# makeblock_stepper_driver.net
KiCad netlist of a schematic drawn in EAGLE
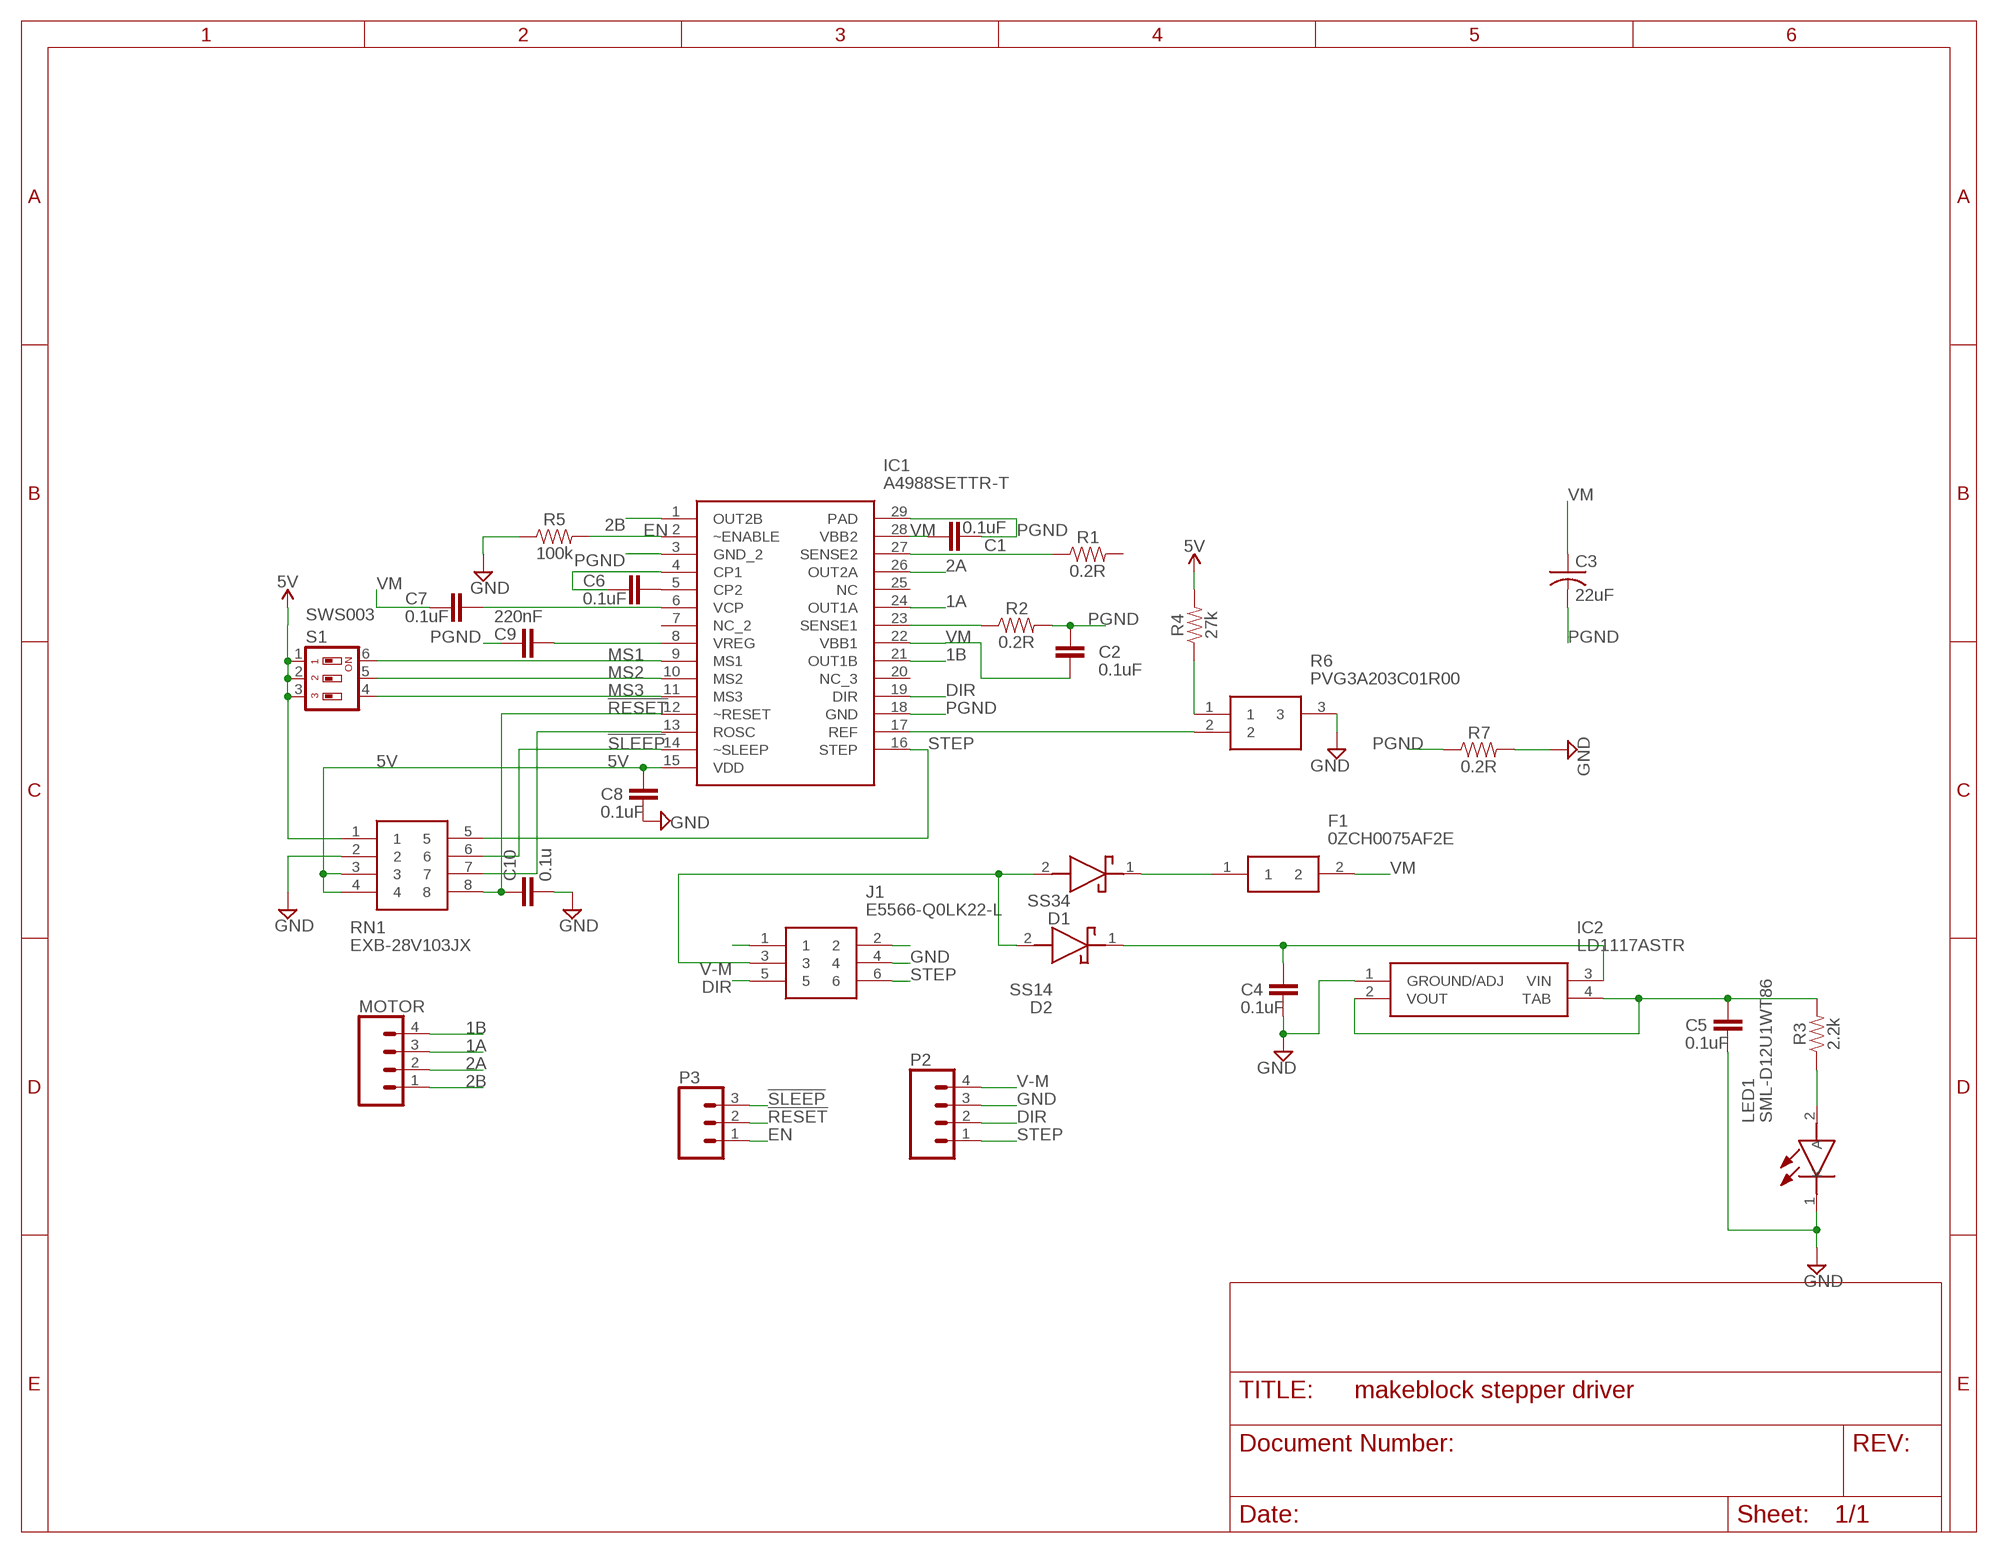
[diagram p0: schematic, sheet 1]

(export (version "E")
  (design (tool "Eeschema 10.0.6"))
  (components
    (comp (ref "C1")
      (value "0.1uF")
      (footprint "eagle-import:C0402")
      (libsource (lib "eagle-import") (part "C-EUC0402"))
    )
    (comp (ref "C2")
      (value "0.1uF")
      (footprint "eagle-import:C0402")
      (libsource (lib "eagle-import") (part "C-EUC0402"))
    )
    (comp (ref "C3")
      (value "22uF")
      (footprint "eagle-import:C025-024X044")
      (libsource (lib "eagle-import") (part "C-US025-024X044"))
    )
    (comp (ref "C4")
      (value "0.1uF")
      (footprint "eagle-import:C0402")
      (libsource (lib "eagle-import") (part "C-EUC0402"))
    )
    (comp (ref "C5")
      (value "0.1uF")
      (footprint "eagle-import:C0402")
      (libsource (lib "eagle-import") (part "C-EUC0402"))
    )
    (comp (ref "C6")
      (value "0.1uF")
      (footprint "eagle-import:C0402")
      (libsource (lib "eagle-import") (part "C-EUC0402"))
    )
    (comp (ref "C7")
      (value "0.1uF")
      (footprint "eagle-import:C0402")
      (libsource (lib "eagle-import") (part "C-EUC0402"))
    )
    (comp (ref "C8")
      (value "0.1uF")
      (footprint "eagle-import:C0402")
      (libsource (lib "eagle-import") (part "C-EUC0402"))
    )
    (comp (ref "C9")
      (value "220nF")
      (footprint "eagle-import:C0402")
      (libsource (lib "eagle-import") (part "C-EUC0402"))
    )
    (comp (ref "C10")
      (value "0.1u")
      (footprint "eagle-import:C0402")
      (libsource (lib "eagle-import") (part "C-EUC0402"))
    )
    (comp (ref "D1")
      (value "SS34")
      (footprint "eagle-import:DIOM8059X256N")
      (fields (field (name "MOUSER_PART_NUMBER") "512-SS34") (field (name "RS_PART_NUMBER") "1662321"))
      (libsource (lib "eagle-import") (part "SS34"))
    )
    (comp (ref "D2")
      (value "SS14")
      (footprint "eagle-import:DIOM5227X270N")
      (fields (field (name "MOUSER_PART_NUMBER") "512-SS14") (field (name "RS_PART_NUMBER") "1662555"))
      (libsource (lib "eagle-import") (part "SS14"))
    )
    (comp (ref "F1")
      (value "0ZCH0075AF2E")
      (footprint "eagle-import:FUSC3226X75N")
      (fields (field (name "MOUSER_PART_NUMBER") "530-0ZCH0075AF2E"))
      (libsource (lib "eagle-import") (part "0ZCH0075AF2E"))
    )
    (comp (ref "IC1")
      (value "A4988SETTR-T")
      (footprint "eagle-import:QFN50P500X500X100-29N")
      (libsource (lib "eagle-import") (part "A4988SETTR-T"))
    )
    (comp (ref "IC2")
      (value "LD1117ASTR")
      (footprint "eagle-import:SOT230P700X180-4N")
      (fields (field (name "MOUSER_PART_NUMBER") "511-LD1117ASTR") (field (name "RS_PART_NUMBER") "7147806"))
      (libsource (lib "eagle-import") (part "LD1117ASTR"))
    )
    (comp (ref "J1")
      (value "E5566-Q0LK22-L")
      (footprint "eagle-import:E5566Q0LK22L")
      (fields (field (name "MOUSER_PART_NUMBER") "673-E5566-Q0LK22-L"))
      (libsource (lib "eagle-import") (part "E5566-Q0LK22-L"))
    )
    (comp (ref "LED1")
      (value "SML-D12U1WT86")
      (footprint "eagle-import:LEDC1608X65N")
      (fields
        (field (name "MOUSER_PART_NUMBER") "755-SML-D12U1WT86")
        (field (name "RS_PART_NUMBER") "1332870")
      )
      (libsource (lib "eagle-import") (part "SML-D12U1WT86"))
    )
    (comp (ref "MOTOR")
      (value "CONN_04JST-PTH-VERT")
      (footprint "eagle-import:JST-4-PTH-VERT")
      (libsource (lib "eagle-import") (part "CONN_04JST-PTH-VERT"))
    )
    (comp (ref "P2")
      (value "CONN_04PTH")
      (footprint "eagle-import:1X04")
      (libsource (lib "eagle-import") (part "CONN_04PTH"))
    )
    (comp (ref "P3")
      (value "CONN_03LOCK")
      (footprint "eagle-import:1X03_LOCK")
      (libsource (lib "eagle-import") (part "CONN_03LOCK"))
    )
    (comp (ref "R1")
      (value "0.2R")
      (footprint "eagle-import:0603")
      (libsource (lib "eagle-import") (part "10MOHM-0603-1/10W-5%"))
    )
    (comp (ref "R2")
      (value "0.2R")
      (footprint "eagle-import:0603")
      (libsource (lib "eagle-import") (part "10MOHM-0603-1/10W-5%"))
    )
    (comp (ref "R3")
      (value "2.2k")
      (footprint "eagle-import:0603")
      (libsource (lib "eagle-import") (part "10MOHM-0603-1/10W-5%"))
    )
    (comp (ref "R4")
      (value "27k")
      (footprint "eagle-import:0603")
      (libsource (lib "eagle-import") (part "10MOHM-0603-1/10W-5%"))
    )
    (comp (ref "R5")
      (value "100k")
      (footprint "eagle-import:0603")
      (libsource (lib "eagle-import") (part "10MOHM-0603-1/10W-5%"))
    )
    (comp (ref "R6")
      (value "PVG3A203C01R00")
      (footprint "eagle-import:PVG3A203C01R00")
      (fields (field (name "RS_PART_NUMBER") "7250053P"))
      (libsource (lib "eagle-import") (part "PVG3A203C01R00"))
    )
    (comp (ref "R7")
      (value "0.2R")
      (footprint "eagle-import:0603")
      (libsource (lib "eagle-import") (part "10MOHM-0603-1/10W-5%"))
    )
    (comp (ref "RN1")
      (value "EXB-28V103JX")
      (footprint "eagle-import:EXB28V_1")
      (fields (field (name "MOUSER_PART_NUMBER") "667-EXB-28V103JX"))
      (libsource (lib "eagle-import") (part "EXB-28V103JX"))
    )
    (comp (ref "S1")
      (value "SWS003")
      (footprint "eagle-import:SMS-003")
      (libsource (lib "eagle-import") (part "SWS003"))
    )
  )
  (nets
    (net (code "1") (name "/1A") (class "Default")
      (node (ref "IC1") (pin "24") (pinfunction "OUT1A_24") (pintype "bidirectional"))
      (node (ref "MOTOR") (pin "3") (pinfunction "3_3") (pintype "passive"))
    )
    (net (code "2") (name "/1B") (class "Default")
      (node (ref "IC1") (pin "21") (pinfunction "OUT1B_21") (pintype "bidirectional"))
      (node (ref "MOTOR") (pin "4") (pinfunction "4_4") (pintype "passive"))
    )
    (net (code "3") (name "/2A") (class "Default")
      (node (ref "IC1") (pin "26") (pinfunction "OUT2A_26") (pintype "bidirectional"))
      (node (ref "MOTOR") (pin "2") (pinfunction "2_2") (pintype "passive"))
    )
    (net (code "4") (name "/2B") (class "Default")
      (node (ref "IC1") (pin "1") (pinfunction "OUT2B_1") (pintype "bidirectional"))
      (node (ref "MOTOR") (pin "1") (pinfunction "1_1") (pintype "passive"))
    )
    (net (code "5") (name "/DIR") (class "Default")
      (node (ref "IC1") (pin "19") (pinfunction "DIR_19") (pintype "bidirectional"))
      (node (ref "J1") (pin "5") (pinfunction "5_5") (pintype "bidirectional"))
      (node (ref "P2") (pin "2") (pinfunction "2_2") (pintype "passive"))
    )
    (net (code "6") (name "/EN") (class "Default")
      (node (ref "IC1") (pin "2") (pinfunction "~{ENABLE}_2") (pintype "bidirectional"))
      (node (ref "P3") (pin "1") (pinfunction "1_1") (pintype "passive"))
      (node (ref "R5") (pin "2") (pinfunction "2_2") (pintype "passive"))
    )
    (net (code "7") (name "/MS1") (class "Default")
      (node (ref "IC1") (pin "9") (pinfunction "MS1_9") (pintype "bidirectional"))
      (node (ref "S1") (pin "6") (pinfunction "6_6") (pintype "passive"))
    )
    (net (code "8") (name "/MS2") (class "Default")
      (node (ref "IC1") (pin "10") (pinfunction "MS2_10") (pintype "bidirectional"))
      (node (ref "S1") (pin "5") (pinfunction "5_5") (pintype "passive"))
    )
    (net (code "9") (name "/MS3") (class "Default")
      (node (ref "IC1") (pin "11") (pinfunction "MS3_11") (pintype "bidirectional"))
      (node (ref "S1") (pin "4") (pinfunction "4_4") (pintype "passive"))
    )
    (net (code "10") (name "/PGND") (class "Default")
      (node (ref "C1") (pin "1") (pinfunction "1_1") (pintype "passive"))
      (node (ref "C2") (pin "1") (pinfunction "1_1") (pintype "passive"))
      (node (ref "C3") (pin "2") (pinfunction "2_2") (pintype "passive"))
      (node (ref "C9") (pin "1") (pinfunction "1_1") (pintype "passive"))
      (node (ref "IC1") (pin "18") (pinfunction "GND_18") (pintype "bidirectional"))
      (node (ref "IC1") (pin "29") (pinfunction "PAD_29") (pintype "bidirectional"))
      (node (ref "IC1") (pin "3") (pinfunction "GND_2_3") (pintype "bidirectional"))
      (node (ref "R2") (pin "2") (pinfunction "2_2") (pintype "passive"))
      (node (ref "R7") (pin "1") (pinfunction "1_1") (pintype "passive"))
    )
    (net (code "11") (name "/STEP") (class "Default")
      (node (ref "IC1") (pin "16") (pinfunction "STEP_16") (pintype "bidirectional"))
      (node (ref "J1") (pin "6") (pinfunction "6_6") (pintype "bidirectional"))
      (node (ref "P2") (pin "1") (pinfunction "1_1") (pintype "passive"))
      (node (ref "RN1") (pin "5") (pinfunction "5_5") (pintype "bidirectional"))
    )
    (net (code "12") (name "/V-M") (class "Default")
      (node (ref "D1") (pin "2") (pinfunction "A_2") (pintype "bidirectional"))
      (node (ref "D2") (pin "2") (pinfunction "A_2") (pintype "bidirectional"))
      (node (ref "J1") (pin "3") (pinfunction "3_3") (pintype "bidirectional"))
      (node (ref "P2") (pin "4") (pinfunction "4_4") (pintype "passive"))
    )
    (net (code "13") (name "/VM") (class "Default")
      (node (ref "C1") (pin "2") (pinfunction "2_2") (pintype "passive"))
      (node (ref "C2") (pin "2") (pinfunction "2_2") (pintype "passive"))
      (node (ref "C3") (pin "1") (pinfunction "1_1") (pintype "passive"))
      (node (ref "C7") (pin "1") (pinfunction "1_1") (pintype "passive"))
      (node (ref "F1") (pin "2") (pinfunction "2_2") (pintype "bidirectional"))
      (node (ref "IC1") (pin "22") (pinfunction "VBB1_22") (pintype "bidirectional"))
      (node (ref "IC1") (pin "28") (pinfunction "VBB2_28") (pintype "bidirectional"))
    )
    (net (code "14") (name "/~{RESET}") (class "Default")
      (node (ref "C10") (pin "1") (pinfunction "1_1") (pintype "passive"))
      (node (ref "IC1") (pin "12") (pinfunction "~{RESET}_12") (pintype "bidirectional"))
      (node (ref "P3") (pin "2") (pinfunction "2_2") (pintype "passive"))
      (node (ref "RN1") (pin "8") (pinfunction "8_8") (pintype "bidirectional"))
    )
    (net (code "15") (name "/~{SLEEP}") (class "Default")
      (node (ref "IC1") (pin "14") (pinfunction "~{SLEEP}_14") (pintype "bidirectional"))
      (node (ref "P3") (pin "3") (pinfunction "3_3") (pintype "passive"))
      (node (ref "RN1") (pin "6") (pinfunction "6_6") (pintype "bidirectional"))
    )
    (net (code "16") (name "5V") (class "Default")
      (node (ref "C8") (pin "2") (pinfunction "2_2") (pintype "passive"))
      (node (ref "IC1") (pin "15") (pinfunction "VDD_15") (pintype "bidirectional"))
      (node (ref "R4") (pin "2") (pinfunction "2_2") (pintype "passive"))
      (node (ref "RN1") (pin "1") (pinfunction "1_1") (pintype "bidirectional"))
      (node (ref "RN1") (pin "3") (pinfunction "3_3") (pintype "bidirectional"))
      (node (ref "RN1") (pin "4") (pinfunction "4_4") (pintype "bidirectional"))
      (node (ref "S1") (pin "1") (pinfunction "1_1") (pintype "passive"))
      (node (ref "S1") (pin "2") (pinfunction "2_2") (pintype "passive"))
      (node (ref "S1") (pin "3") (pinfunction "3_3") (pintype "passive"))
    )
    (net (code "17") (name "GND") (class "Default")
      (node (ref "C10") (pin "2") (pinfunction "2_2") (pintype "passive"))
      (node (ref "C4") (pin "1") (pinfunction "1_1") (pintype "passive"))
      (node (ref "C5") (pin "1") (pinfunction "1_1") (pintype "passive"))
      (node (ref "C8") (pin "1") (pinfunction "1_1") (pintype "passive"))
      (node (ref "IC2") (pin "1") (pinfunction "GROUND/ADJ_1") (pintype "bidirectional"))
      (node (ref "J1") (pin "4") (pinfunction "4_4") (pintype "bidirectional"))
      (node (ref "LED1") (pin "1") (pinfunction "K_1") (pintype "bidirectional"))
      (node (ref "P2") (pin "3") (pinfunction "3_3") (pintype "passive"))
      (node (ref "R5") (pin "1") (pinfunction "1_1") (pintype "passive"))
      (node (ref "R6") (pin "3") (pinfunction "3_3") (pintype "bidirectional"))
      (node (ref "R7") (pin "2") (pinfunction "2_2") (pintype "passive"))
      (node (ref "RN1") (pin "2") (pinfunction "2_2") (pintype "bidirectional"))
    )
    (net (code "18") (name "Net-(D1-K)") (class "Default")
      (node (ref "D1") (pin "1") (pinfunction "K_1") (pintype "bidirectional"))
      (node (ref "F1") (pin "1") (pinfunction "1_1") (pintype "bidirectional"))
    )
    (net (code "19") (name "Net-(D2-K)") (class "Default")
      (node (ref "C4") (pin "2") (pinfunction "2_2") (pintype "passive"))
      (node (ref "D2") (pin "1") (pinfunction "K_1") (pintype "bidirectional"))
      (node (ref "IC2") (pin "3") (pinfunction "VIN_3") (pintype "input"))
    )
    (net (code "20") (name "Net-(IC1-CP1)") (class "Default")
      (node (ref "C6") (pin "1") (pinfunction "1_1") (pintype "passive"))
      (node (ref "IC1") (pin "4") (pinfunction "CP1_4") (pintype "bidirectional"))
    )
    (net (code "21") (name "Net-(IC1-CP2)") (class "Default")
      (node (ref "C6") (pin "2") (pinfunction "2_2") (pintype "passive"))
      (node (ref "IC1") (pin "5") (pinfunction "CP2_5") (pintype "bidirectional"))
    )
    (net (code "22") (name "Net-(IC1-REF)") (class "Default")
      (node (ref "IC1") (pin "17") (pinfunction "REF_17") (pintype "bidirectional"))
      (node (ref "R6") (pin "2") (pinfunction "2_2") (pintype "bidirectional"))
    )
    (net (code "23") (name "Net-(IC1-ROSC)") (class "Default")
      (node (ref "IC1") (pin "13") (pinfunction "ROSC_13") (pintype "bidirectional"))
      (node (ref "RN1") (pin "7") (pinfunction "7_7") (pintype "bidirectional"))
    )
    (net (code "24") (name "Net-(IC1-SENSE1)") (class "Default")
      (node (ref "IC1") (pin "23") (pinfunction "SENSE1_23") (pintype "bidirectional"))
      (node (ref "R2") (pin "1") (pinfunction "1_1") (pintype "passive"))
    )
    (net (code "25") (name "Net-(IC1-SENSE2)") (class "Default")
      (node (ref "IC1") (pin "27") (pinfunction "SENSE2_27") (pintype "bidirectional"))
      (node (ref "R1") (pin "1") (pinfunction "1_1") (pintype "passive"))
    )
    (net (code "26") (name "Net-(IC1-VCP)") (class "Default")
      (node (ref "C7") (pin "2") (pinfunction "2_2") (pintype "passive"))
      (node (ref "IC1") (pin "6") (pinfunction "VCP_6") (pintype "bidirectional"))
    )
    (net (code "27") (name "Net-(IC1-VREG)") (class "Default")
      (node (ref "C9") (pin "2") (pinfunction "2_2") (pintype "passive"))
      (node (ref "IC1") (pin "8") (pinfunction "VREG_8") (pintype "bidirectional"))
    )
    (net (code "28") (name "Net-(IC2-TAB)") (class "Default")
      (node (ref "C5") (pin "2") (pinfunction "2_2") (pintype "passive"))
      (node (ref "IC2") (pin "2") (pinfunction "VOUT_2") (pintype "output"))
      (node (ref "IC2") (pin "4") (pinfunction "TAB_4") (pintype "bidirectional"))
      (node (ref "R3") (pin "2") (pinfunction "2_2") (pintype "passive"))
    )
    (net (code "29") (name "Net-(LED1-A)") (class "Default")
      (node (ref "LED1") (pin "2") (pinfunction "A_2") (pintype "bidirectional"))
      (node (ref "R3") (pin "1") (pinfunction "1_1") (pintype "passive"))
    )
    (net (code "30") (name "Net-(R4-Pad1)") (class "Default")
      (node (ref "R4") (pin "1") (pinfunction "1_1") (pintype "passive"))
      (node (ref "R6") (pin "1") (pinfunction "1_1") (pintype "bidirectional"))
    )
    (net (code "31") (name "unconnected-(IC1-NC-Pad25)") (class "Default")
      (node (ref "IC1") (pin "25") (pinfunction "NC_25") (pintype "no_connect"))
    )
    (net (code "32") (name "unconnected-(IC1-NC_2-Pad7)") (class "Default")
      (node (ref "IC1") (pin "7") (pinfunction "NC_2_7") (pintype "bidirectional"))
    )
    (net (code "33") (name "unconnected-(IC1-NC_3-Pad20)") (class "Default")
      (node (ref "IC1") (pin "20") (pinfunction "NC_3_20") (pintype "bidirectional"))
    )
    (net (code "34") (name "unconnected-(J1-Pad1)") (class "Default")
      (node (ref "J1") (pin "1") (pinfunction "1_1") (pintype "bidirectional"))
    )
    (net (code "35") (name "unconnected-(J1-Pad2)") (class "Default")
      (node (ref "J1") (pin "2") (pinfunction "2_2") (pintype "bidirectional"))
    )
    (net (code "36") (name "unconnected-(R1-Pad2)") (class "Default")
      (node (ref "R1") (pin "2") (pinfunction "2_2") (pintype "passive"))
    )
  )
)
